# 4_viper_eagle_modern_periferals.net
KiCad netlist of a schematic drawn in Altium Designer
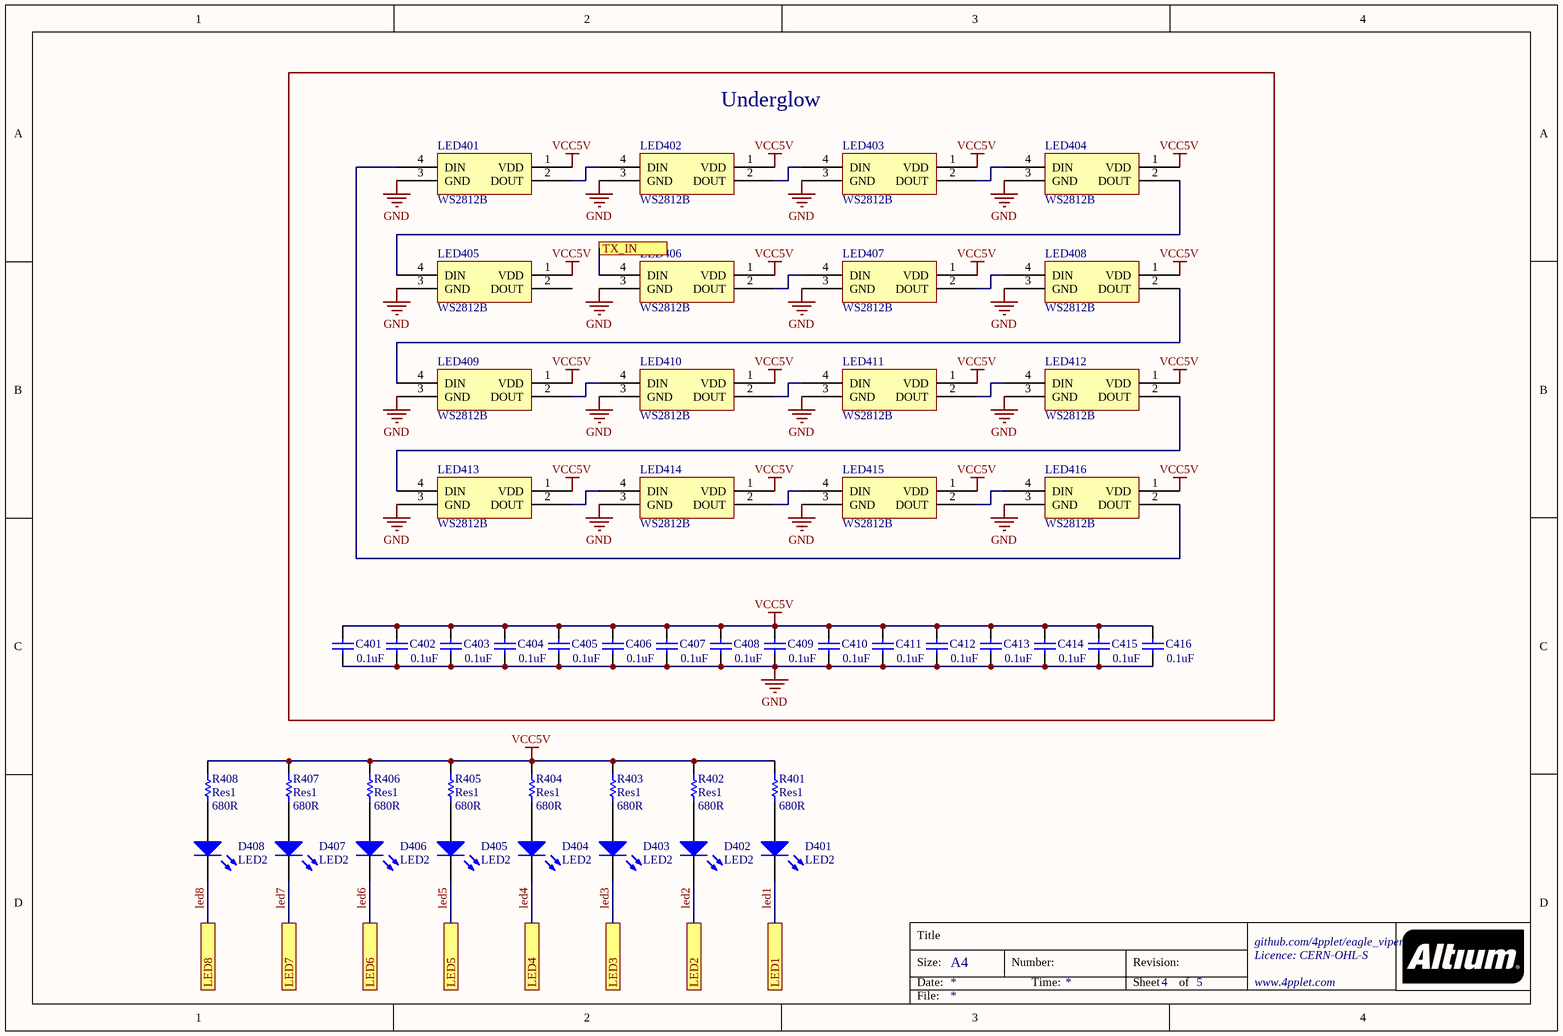
[diagram p0: 4_viper_eagle_modern_periferals.SchDoc]

(export (version "E")
  (design (tool "Eeschema 10.0.6"))
  (components
    (comp (ref "C401")
      (value "0.1uF")
      (footprint "C0603[1608]")
      (description "Capacitor")
      (fields (field (name "MFG") "KEMET") (field (name "LCSC PART #") "C14663"))
      (libsource (lib "Miscellaneous Devices") (part "Cap"))
    )
    (comp (ref "C402")
      (value "0.1uF")
      (footprint "C0603[1608]")
      (description "Capacitor")
      (fields (field (name "MFG") "KEMET") (field (name "LCSC PART #") "C14663"))
      (libsource (lib "Miscellaneous Devices") (part "Cap"))
    )
    (comp (ref "C403")
      (value "0.1uF")
      (footprint "C0603[1608]")
      (description "Capacitor")
      (fields (field (name "MFG") "KEMET") (field (name "LCSC PART #") "C14663"))
      (libsource (lib "Miscellaneous Devices") (part "Cap"))
    )
    (comp (ref "C404")
      (value "0.1uF")
      (footprint "C0603[1608]")
      (description "Capacitor")
      (fields (field (name "MFG") "KEMET") (field (name "LCSC PART #") "C14663"))
      (libsource (lib "Miscellaneous Devices") (part "Cap"))
    )
    (comp (ref "C405")
      (value "0.1uF")
      (footprint "C0603[1608]")
      (description "Capacitor")
      (fields (field (name "MFG") "KEMET") (field (name "LCSC PART #") "C14663"))
      (libsource (lib "Miscellaneous Devices") (part "Cap"))
    )
    (comp (ref "C406")
      (value "0.1uF")
      (footprint "C0603[1608]")
      (description "Capacitor")
      (fields (field (name "MFG") "KEMET") (field (name "LCSC PART #") "C14663"))
      (libsource (lib "Miscellaneous Devices") (part "Cap"))
    )
    (comp (ref "C407")
      (value "0.1uF")
      (footprint "C0603[1608]")
      (description "Capacitor")
      (fields (field (name "MFG") "KEMET") (field (name "LCSC PART #") "C14663"))
      (libsource (lib "Miscellaneous Devices") (part "Cap"))
    )
    (comp (ref "C408")
      (value "0.1uF")
      (footprint "C0603[1608]")
      (description "Capacitor")
      (fields (field (name "MFG") "KEMET") (field (name "LCSC PART #") "C14663"))
      (libsource (lib "Miscellaneous Devices") (part "Cap"))
    )
    (comp (ref "C409")
      (value "0.1uF")
      (footprint "C0603[1608]")
      (description "Capacitor")
      (fields (field (name "MFG") "KEMET") (field (name "LCSC PART #") "C14663"))
      (libsource (lib "Miscellaneous Devices") (part "Cap"))
    )
    (comp (ref "C410")
      (value "0.1uF")
      (footprint "C0603[1608]")
      (description "Capacitor")
      (fields (field (name "MFG") "KEMET") (field (name "LCSC PART #") "C14663"))
      (libsource (lib "Miscellaneous Devices") (part "Cap"))
    )
    (comp (ref "C411")
      (value "0.1uF")
      (footprint "C0603[1608]")
      (description "Capacitor")
      (fields (field (name "MFG") "KEMET") (field (name "LCSC PART #") "C14663"))
      (libsource (lib "Miscellaneous Devices") (part "Cap"))
    )
    (comp (ref "C412")
      (value "0.1uF")
      (footprint "C0603[1608]")
      (description "Capacitor")
      (fields (field (name "MFG") "KEMET") (field (name "LCSC PART #") "C14663"))
      (libsource (lib "Miscellaneous Devices") (part "Cap"))
    )
    (comp (ref "C413")
      (value "0.1uF")
      (footprint "C0603[1608]")
      (description "Capacitor")
      (fields (field (name "MFG") "KEMET") (field (name "LCSC PART #") "C14663"))
      (libsource (lib "Miscellaneous Devices") (part "Cap"))
    )
    (comp (ref "C414")
      (value "0.1uF")
      (footprint "C0603[1608]")
      (description "Capacitor")
      (fields (field (name "MFG") "KEMET") (field (name "LCSC PART #") "C14663"))
      (libsource (lib "Miscellaneous Devices") (part "Cap"))
    )
    (comp (ref "C415")
      (value "0.1uF")
      (footprint "C0603[1608]")
      (description "Capacitor")
      (fields (field (name "MFG") "KEMET") (field (name "LCSC PART #") "C14663"))
      (libsource (lib "Miscellaneous Devices") (part "Cap"))
    )
    (comp (ref "C416")
      (value "0.1uF")
      (footprint "C0603[1608]")
      (description "Capacitor")
      (fields (field (name "MFG") "KEMET") (field (name "LCSC PART #") "C14663"))
      (libsource (lib "Miscellaneous Devices") (part "Cap"))
    )
    (comp (ref "D401")
      (value "LED2")
      (footprint "LED - THT")
      (description "Typical RED, GREEN, YELLOW, AMBER GaAs LED")
      (libsource (lib "Miscellaneous Devices") (part "LED2"))
    )
    (comp (ref "D402")
      (value "LED2")
      (footprint "LED - THT")
      (description "Typical RED, GREEN, YELLOW, AMBER GaAs LED")
      (libsource (lib "Miscellaneous Devices") (part "LED2"))
    )
    (comp (ref "D403")
      (value "LED2")
      (footprint "LED - THT")
      (description "Typical RED, GREEN, YELLOW, AMBER GaAs LED")
      (libsource (lib "Miscellaneous Devices") (part "LED2"))
    )
    (comp (ref "D404")
      (value "LED2")
      (footprint "LED - THT")
      (description "Typical RED, GREEN, YELLOW, AMBER GaAs LED")
      (libsource (lib "Miscellaneous Devices") (part "LED2"))
    )
    (comp (ref "D405")
      (value "LED2")
      (footprint "LED - THT")
      (description "Typical RED, GREEN, YELLOW, AMBER GaAs LED")
      (libsource (lib "Miscellaneous Devices") (part "LED2"))
    )
    (comp (ref "D406")
      (value "LED2")
      (footprint "LED - THT")
      (description "Typical RED, GREEN, YELLOW, AMBER GaAs LED")
      (libsource (lib "Miscellaneous Devices") (part "LED2"))
    )
    (comp (ref "D407")
      (value "LED2")
      (footprint "LED - THT")
      (description "Typical RED, GREEN, YELLOW, AMBER GaAs LED")
      (libsource (lib "Miscellaneous Devices") (part "LED2"))
    )
    (comp (ref "D408")
      (value "LED2")
      (footprint "LED - THT")
      (description "Typical RED, GREEN, YELLOW, AMBER GaAs LED")
      (libsource (lib "Miscellaneous Devices") (part "LED2"))
    )
    (comp (ref "LED401")
      (value "WS2812B")
      (footprint "WS2812B")
      (fields (field (name "LCSC PART #") "C114586") (field (name "MRF.PART") "WS2812B-B"))
      (libsource (lib "Keebs") (part "WS2812B"))
    )
    (comp (ref "LED402")
      (value "WS2812B")
      (footprint "WS2812B")
      (fields (field (name "LCSC PART #") "C114586") (field (name "MRF.PART") "WS2812B-B"))
      (libsource (lib "Keebs") (part "WS2812B"))
    )
    (comp (ref "LED403")
      (value "WS2812B")
      (footprint "WS2812B")
      (fields (field (name "LCSC PART #") "C114586") (field (name "MRF.PART") "WS2812B-B"))
      (libsource (lib "Keebs") (part "WS2812B"))
    )
    (comp (ref "LED404")
      (value "WS2812B")
      (footprint "WS2812B")
      (fields (field (name "LCSC PART #") "C114586") (field (name "MRF.PART") "WS2812B-B"))
      (libsource (lib "Keebs") (part "WS2812B"))
    )
    (comp (ref "LED405")
      (value "WS2812B")
      (footprint "WS2812B")
      (fields (field (name "LCSC PART #") "C114586") (field (name "MRF.PART") "WS2812B-B"))
      (libsource (lib "Keebs") (part "WS2812B"))
    )
    (comp (ref "LED406")
      (value "WS2812B")
      (footprint "WS2812B")
      (fields (field (name "LCSC PART #") "C114586") (field (name "MRF.PART") "WS2812B-B"))
      (libsource (lib "Keebs") (part "WS2812B"))
    )
    (comp (ref "LED407")
      (value "WS2812B")
      (footprint "WS2812B")
      (fields (field (name "LCSC PART #") "C114586") (field (name "MRF.PART") "WS2812B-B"))
      (libsource (lib "Keebs") (part "WS2812B"))
    )
    (comp (ref "LED408")
      (value "WS2812B")
      (footprint "WS2812B")
      (fields (field (name "LCSC PART #") "C114586") (field (name "MRF.PART") "WS2812B-B"))
      (libsource (lib "Keebs") (part "WS2812B"))
    )
    (comp (ref "LED409")
      (value "WS2812B")
      (footprint "WS2812B")
      (fields (field (name "LCSC PART #") "C114586") (field (name "MRF.PART") "WS2812B-B"))
      (libsource (lib "Keebs") (part "WS2812B"))
    )
    (comp (ref "LED410")
      (value "WS2812B")
      (footprint "WS2812B")
      (fields (field (name "LCSC PART #") "C114586") (field (name "MRF.PART") "WS2812B-B"))
      (libsource (lib "Keebs") (part "WS2812B"))
    )
    (comp (ref "LED411")
      (value "WS2812B")
      (footprint "WS2812B")
      (fields (field (name "LCSC PART #") "C114586") (field (name "MRF.PART") "WS2812B-B"))
      (libsource (lib "Keebs") (part "WS2812B"))
    )
    (comp (ref "LED412")
      (value "WS2812B")
      (footprint "WS2812B")
      (fields (field (name "LCSC PART #") "C114586") (field (name "MRF.PART") "WS2812B-B"))
      (libsource (lib "Keebs") (part "WS2812B"))
    )
    (comp (ref "LED413")
      (value "WS2812B")
      (footprint "WS2812B")
      (fields (field (name "LCSC PART #") "C114586") (field (name "MRF.PART") "WS2812B-B"))
      (libsource (lib "Keebs") (part "WS2812B"))
    )
    (comp (ref "LED414")
      (value "WS2812B")
      (footprint "WS2812B")
      (fields (field (name "LCSC PART #") "C114586") (field (name "MRF.PART") "WS2812B-B"))
      (libsource (lib "Keebs") (part "WS2812B"))
    )
    (comp (ref "LED415")
      (value "WS2812B")
      (footprint "WS2812B")
      (fields (field (name "LCSC PART #") "C114586") (field (name "MRF.PART") "WS2812B-B"))
      (libsource (lib "Keebs") (part "WS2812B"))
    )
    (comp (ref "LED416")
      (value "WS2812B")
      (footprint "WS2812B")
      (fields (field (name "LCSC PART #") "C114586") (field (name "MRF.PART") "WS2812B-B"))
      (libsource (lib "Keebs") (part "WS2812B"))
    )
    (comp (ref "R401")
      (value "Res1")
      (footprint "R0603[1608]")
      (description "Resistor")
      (fields
        (field (name "ALTIUM_VALUE") "680R")
        (field (name "LCSC PART #") "C23228")
        (field (name "MRF.PART") "0603WAF6800T5E")
      )
      (libsource (lib "Miscellaneous Devices") (part "Res1"))
    )
    (comp (ref "R402")
      (value "Res1")
      (footprint "R0603[1608]")
      (description "Resistor")
      (fields
        (field (name "ALTIUM_VALUE") "680R")
        (field (name "LCSC PART #") "C23228")
        (field (name "MRF.PART") "0603WAF6800T5E")
      )
      (libsource (lib "Miscellaneous Devices") (part "Res1"))
    )
    (comp (ref "R403")
      (value "Res1")
      (footprint "R0603[1608]")
      (description "Resistor")
      (fields
        (field (name "ALTIUM_VALUE") "680R")
        (field (name "LCSC PART #") "C23228")
        (field (name "MRF.PART") "0603WAF6800T5E")
      )
      (libsource (lib "Miscellaneous Devices") (part "Res1"))
    )
    (comp (ref "R404")
      (value "Res1")
      (footprint "R0603[1608]")
      (description "Resistor")
      (fields
        (field (name "ALTIUM_VALUE") "680R")
        (field (name "LCSC PART #") "C23228")
        (field (name "MRF.PART") "0603WAF6800T5E")
      )
      (libsource (lib "Miscellaneous Devices") (part "Res1"))
    )
    (comp (ref "R405")
      (value "Res1")
      (footprint "R0603[1608]")
      (description "Resistor")
      (fields
        (field (name "ALTIUM_VALUE") "680R")
        (field (name "LCSC PART #") "C23228")
        (field (name "MRF.PART") "0603WAF6800T5E")
      )
      (libsource (lib "Miscellaneous Devices") (part "Res1"))
    )
    (comp (ref "R406")
      (value "Res1")
      (footprint "R0603[1608]")
      (description "Resistor")
      (fields
        (field (name "ALTIUM_VALUE") "680R")
        (field (name "LCSC PART #") "C23228")
        (field (name "MRF.PART") "0603WAF6800T5E")
      )
      (libsource (lib "Miscellaneous Devices") (part "Res1"))
    )
    (comp (ref "R407")
      (value "Res1")
      (footprint "R0603[1608]")
      (description "Resistor")
      (fields
        (field (name "ALTIUM_VALUE") "680R")
        (field (name "LCSC PART #") "C23228")
        (field (name "MRF.PART") "0603WAF6800T5E")
      )
      (libsource (lib "Miscellaneous Devices") (part "Res1"))
    )
    (comp (ref "R408")
      (value "Res1")
      (footprint "R0603[1608]")
      (description "Resistor")
      (fields
        (field (name "ALTIUM_VALUE") "680R")
        (field (name "LCSC PART #") "C23228")
        (field (name "MRF.PART") "0603WAF6800T5E")
      )
      (libsource (lib "Miscellaneous Devices") (part "Res1"))
    )
  )
  (nets
    (net (code "1") (name "/TX_IN") (class "Default")
      (node (ref "LED406") (pin "4") (pinfunction "DIN_4") (pintype "passive"))
    )
    (net (code "2") (name "/led1") (class "Default")
      (node (ref "D401") (pin "2") (pinfunction "K_2") (pintype "passive"))
    )
    (net (code "3") (name "/led2") (class "Default")
      (node (ref "D402") (pin "2") (pinfunction "K_2") (pintype "passive"))
    )
    (net (code "4") (name "/led3") (class "Default")
      (node (ref "D403") (pin "2") (pinfunction "K_2") (pintype "passive"))
    )
    (net (code "5") (name "/led4") (class "Default")
      (node (ref "D404") (pin "2") (pinfunction "K_2") (pintype "passive"))
    )
    (net (code "6") (name "/led5") (class "Default")
      (node (ref "D405") (pin "2") (pinfunction "K_2") (pintype "passive"))
    )
    (net (code "7") (name "/led6") (class "Default")
      (node (ref "D406") (pin "2") (pinfunction "K_2") (pintype "passive"))
    )
    (net (code "8") (name "/led7") (class "Default")
      (node (ref "D407") (pin "2") (pinfunction "K_2") (pintype "passive"))
    )
    (net (code "9") (name "/led8") (class "Default")
      (node (ref "D408") (pin "2") (pinfunction "K_2") (pintype "passive"))
    )
    (net (code "10") (name "GND") (class "Default")
      (node (ref "C401") (pin "1") (pinfunction "1_1") (pintype "passive"))
      (node (ref "C402") (pin "1") (pinfunction "1_1") (pintype "passive"))
      (node (ref "C403") (pin "1") (pinfunction "1_1") (pintype "passive"))
      (node (ref "C404") (pin "1") (pinfunction "1_1") (pintype "passive"))
      (node (ref "C405") (pin "1") (pinfunction "1_1") (pintype "passive"))
      (node (ref "C406") (pin "1") (pinfunction "1_1") (pintype "passive"))
      (node (ref "C407") (pin "1") (pinfunction "1_1") (pintype "passive"))
      (node (ref "C408") (pin "1") (pinfunction "1_1") (pintype "passive"))
      (node (ref "C409") (pin "1") (pinfunction "1_1") (pintype "passive"))
      (node (ref "C410") (pin "1") (pinfunction "1_1") (pintype "passive"))
      (node (ref "C411") (pin "1") (pinfunction "1_1") (pintype "passive"))
      (node (ref "C412") (pin "1") (pinfunction "1_1") (pintype "passive"))
      (node (ref "C413") (pin "1") (pinfunction "1_1") (pintype "passive"))
      (node (ref "C414") (pin "1") (pinfunction "1_1") (pintype "passive"))
      (node (ref "C415") (pin "1") (pinfunction "1_1") (pintype "passive"))
      (node (ref "C416") (pin "1") (pinfunction "1_1") (pintype "passive"))
      (node (ref "LED401") (pin "3") (pinfunction "GND_3") (pintype "passive"))
      (node (ref "LED402") (pin "3") (pinfunction "GND_3") (pintype "passive"))
      (node (ref "LED403") (pin "3") (pinfunction "GND_3") (pintype "passive"))
      (node (ref "LED404") (pin "3") (pinfunction "GND_3") (pintype "passive"))
      (node (ref "LED405") (pin "3") (pinfunction "GND_3") (pintype "passive"))
      (node (ref "LED406") (pin "3") (pinfunction "GND_3") (pintype "passive"))
      (node (ref "LED407") (pin "3") (pinfunction "GND_3") (pintype "passive"))
      (node (ref "LED408") (pin "3") (pinfunction "GND_3") (pintype "passive"))
      (node (ref "LED409") (pin "3") (pinfunction "GND_3") (pintype "passive"))
      (node (ref "LED410") (pin "3") (pinfunction "GND_3") (pintype "passive"))
      (node (ref "LED411") (pin "3") (pinfunction "GND_3") (pintype "passive"))
      (node (ref "LED412") (pin "3") (pinfunction "GND_3") (pintype "passive"))
      (node (ref "LED413") (pin "3") (pinfunction "GND_3") (pintype "passive"))
      (node (ref "LED414") (pin "3") (pinfunction "GND_3") (pintype "passive"))
      (node (ref "LED415") (pin "3") (pinfunction "GND_3") (pintype "passive"))
      (node (ref "LED416") (pin "3") (pinfunction "GND_3") (pintype "passive"))
    )
    (net (code "11") (name "Net-(D401-A)") (class "Default")
      (node (ref "D401") (pin "1") (pinfunction "A_1") (pintype "passive"))
      (node (ref "R401") (pin "2") (pinfunction "2_2") (pintype "passive"))
    )
    (net (code "12") (name "Net-(D402-A)") (class "Default")
      (node (ref "D402") (pin "1") (pinfunction "A_1") (pintype "passive"))
      (node (ref "R402") (pin "2") (pinfunction "2_2") (pintype "passive"))
    )
    (net (code "13") (name "Net-(D403-A)") (class "Default")
      (node (ref "D403") (pin "1") (pinfunction "A_1") (pintype "passive"))
      (node (ref "R403") (pin "2") (pinfunction "2_2") (pintype "passive"))
    )
    (net (code "14") (name "Net-(D404-A)") (class "Default")
      (node (ref "D404") (pin "1") (pinfunction "A_1") (pintype "passive"))
      (node (ref "R404") (pin "2") (pinfunction "2_2") (pintype "passive"))
    )
    (net (code "15") (name "Net-(D405-A)") (class "Default")
      (node (ref "D405") (pin "1") (pinfunction "A_1") (pintype "passive"))
      (node (ref "R405") (pin "2") (pinfunction "2_2") (pintype "passive"))
    )
    (net (code "16") (name "Net-(D406-A)") (class "Default")
      (node (ref "D406") (pin "1") (pinfunction "A_1") (pintype "passive"))
      (node (ref "R406") (pin "2") (pinfunction "2_2") (pintype "passive"))
    )
    (net (code "17") (name "Net-(D407-A)") (class "Default")
      (node (ref "D407") (pin "1") (pinfunction "A_1") (pintype "passive"))
      (node (ref "R407") (pin "2") (pinfunction "2_2") (pintype "passive"))
    )
    (net (code "18") (name "Net-(D408-A)") (class "Default")
      (node (ref "D408") (pin "1") (pinfunction "A_1") (pintype "passive"))
      (node (ref "R408") (pin "2") (pinfunction "2_2") (pintype "passive"))
    )
    (net (code "19") (name "Net-(LED401-DIN)") (class "Default")
      (node (ref "LED401") (pin "4") (pinfunction "DIN_4") (pintype "passive"))
      (node (ref "LED416") (pin "2") (pinfunction "DOUT_2") (pintype "passive"))
    )
    (net (code "20") (name "Net-(LED401-DOUT)") (class "Default")
      (node (ref "LED401") (pin "2") (pinfunction "DOUT_2") (pintype "passive"))
      (node (ref "LED402") (pin "4") (pinfunction "DIN_4") (pintype "passive"))
    )
    (net (code "21") (name "Net-(LED402-DOUT)") (class "Default")
      (node (ref "LED402") (pin "2") (pinfunction "DOUT_2") (pintype "passive"))
      (node (ref "LED403") (pin "4") (pinfunction "DIN_4") (pintype "passive"))
    )
    (net (code "22") (name "Net-(LED403-DOUT)") (class "Default")
      (node (ref "LED403") (pin "2") (pinfunction "DOUT_2") (pintype "passive"))
      (node (ref "LED404") (pin "4") (pinfunction "DIN_4") (pintype "passive"))
    )
    (net (code "23") (name "Net-(LED404-DOUT)") (class "Default")
      (node (ref "LED404") (pin "2") (pinfunction "DOUT_2") (pintype "passive"))
      (node (ref "LED405") (pin "4") (pinfunction "DIN_4") (pintype "passive"))
    )
    (net (code "24") (name "Net-(LED406-DOUT)") (class "Default")
      (node (ref "LED406") (pin "2") (pinfunction "DOUT_2") (pintype "passive"))
      (node (ref "LED407") (pin "4") (pinfunction "DIN_4") (pintype "passive"))
    )
    (net (code "25") (name "Net-(LED407-DOUT)") (class "Default")
      (node (ref "LED407") (pin "2") (pinfunction "DOUT_2") (pintype "passive"))
      (node (ref "LED408") (pin "4") (pinfunction "DIN_4") (pintype "passive"))
    )
    (net (code "26") (name "Net-(LED408-DOUT)") (class "Default")
      (node (ref "LED408") (pin "2") (pinfunction "DOUT_2") (pintype "passive"))
      (node (ref "LED409") (pin "4") (pinfunction "DIN_4") (pintype "passive"))
    )
    (net (code "27") (name "Net-(LED409-DOUT)") (class "Default")
      (node (ref "LED409") (pin "2") (pinfunction "DOUT_2") (pintype "passive"))
      (node (ref "LED410") (pin "4") (pinfunction "DIN_4") (pintype "passive"))
    )
    (net (code "28") (name "Net-(LED410-DOUT)") (class "Default")
      (node (ref "LED410") (pin "2") (pinfunction "DOUT_2") (pintype "passive"))
      (node (ref "LED411") (pin "4") (pinfunction "DIN_4") (pintype "passive"))
    )
    (net (code "29") (name "Net-(LED411-DOUT)") (class "Default")
      (node (ref "LED411") (pin "2") (pinfunction "DOUT_2") (pintype "passive"))
      (node (ref "LED412") (pin "4") (pinfunction "DIN_4") (pintype "passive"))
    )
    (net (code "30") (name "Net-(LED412-DOUT)") (class "Default")
      (node (ref "LED412") (pin "2") (pinfunction "DOUT_2") (pintype "passive"))
      (node (ref "LED413") (pin "4") (pinfunction "DIN_4") (pintype "passive"))
    )
    (net (code "31") (name "Net-(LED413-DOUT)") (class "Default")
      (node (ref "LED413") (pin "2") (pinfunction "DOUT_2") (pintype "passive"))
      (node (ref "LED414") (pin "4") (pinfunction "DIN_4") (pintype "passive"))
    )
    (net (code "32") (name "Net-(LED414-DOUT)") (class "Default")
      (node (ref "LED414") (pin "2") (pinfunction "DOUT_2") (pintype "passive"))
      (node (ref "LED415") (pin "4") (pinfunction "DIN_4") (pintype "passive"))
    )
    (net (code "33") (name "Net-(LED415-DOUT)") (class "Default")
      (node (ref "LED415") (pin "2") (pinfunction "DOUT_2") (pintype "passive"))
      (node (ref "LED416") (pin "4") (pinfunction "DIN_4") (pintype "passive"))
    )
    (net (code "34") (name "VCC5V") (class "Default")
      (node (ref "C401") (pin "2") (pinfunction "2_2") (pintype "passive"))
      (node (ref "C402") (pin "2") (pinfunction "2_2") (pintype "passive"))
      (node (ref "C403") (pin "2") (pinfunction "2_2") (pintype "passive"))
      (node (ref "C404") (pin "2") (pinfunction "2_2") (pintype "passive"))
      (node (ref "C405") (pin "2") (pinfunction "2_2") (pintype "passive"))
      (node (ref "C406") (pin "2") (pinfunction "2_2") (pintype "passive"))
      (node (ref "C407") (pin "2") (pinfunction "2_2") (pintype "passive"))
      (node (ref "C408") (pin "2") (pinfunction "2_2") (pintype "passive"))
      (node (ref "C409") (pin "2") (pinfunction "2_2") (pintype "passive"))
      (node (ref "C410") (pin "2") (pinfunction "2_2") (pintype "passive"))
      (node (ref "C411") (pin "2") (pinfunction "2_2") (pintype "passive"))
      (node (ref "C412") (pin "2") (pinfunction "2_2") (pintype "passive"))
      (node (ref "C413") (pin "2") (pinfunction "2_2") (pintype "passive"))
      (node (ref "C414") (pin "2") (pinfunction "2_2") (pintype "passive"))
      (node (ref "C415") (pin "2") (pinfunction "2_2") (pintype "passive"))
      (node (ref "C416") (pin "2") (pinfunction "2_2") (pintype "passive"))
      (node (ref "LED401") (pin "1") (pinfunction "VDD_1") (pintype "passive"))
      (node (ref "LED402") (pin "1") (pinfunction "VDD_1") (pintype "passive"))
      (node (ref "LED403") (pin "1") (pinfunction "VDD_1") (pintype "passive"))
      (node (ref "LED404") (pin "1") (pinfunction "VDD_1") (pintype "passive"))
      (node (ref "LED405") (pin "1") (pinfunction "VDD_1") (pintype "passive"))
      (node (ref "LED406") (pin "1") (pinfunction "VDD_1") (pintype "passive"))
      (node (ref "LED407") (pin "1") (pinfunction "VDD_1") (pintype "passive"))
      (node (ref "LED408") (pin "1") (pinfunction "VDD_1") (pintype "passive"))
      (node (ref "LED409") (pin "1") (pinfunction "VDD_1") (pintype "passive"))
      (node (ref "LED410") (pin "1") (pinfunction "VDD_1") (pintype "passive"))
      (node (ref "LED411") (pin "1") (pinfunction "VDD_1") (pintype "passive"))
      (node (ref "LED412") (pin "1") (pinfunction "VDD_1") (pintype "passive"))
      (node (ref "LED413") (pin "1") (pinfunction "VDD_1") (pintype "passive"))
      (node (ref "LED414") (pin "1") (pinfunction "VDD_1") (pintype "passive"))
      (node (ref "LED415") (pin "1") (pinfunction "VDD_1") (pintype "passive"))
      (node (ref "LED416") (pin "1") (pinfunction "VDD_1") (pintype "passive"))
      (node (ref "R401") (pin "1") (pinfunction "1_1") (pintype "passive"))
      (node (ref "R402") (pin "1") (pinfunction "1_1") (pintype "passive"))
      (node (ref "R403") (pin "1") (pinfunction "1_1") (pintype "passive"))
      (node (ref "R404") (pin "1") (pinfunction "1_1") (pintype "passive"))
      (node (ref "R405") (pin "1") (pinfunction "1_1") (pintype "passive"))
      (node (ref "R406") (pin "1") (pinfunction "1_1") (pintype "passive"))
      (node (ref "R407") (pin "1") (pinfunction "1_1") (pintype "passive"))
      (node (ref "R408") (pin "1") (pinfunction "1_1") (pintype "passive"))
    )
    (net (code "35") (name "unconnected-(LED405-DOUT-Pad2)") (class "Default")
      (node (ref "LED405") (pin "2") (pinfunction "DOUT_2") (pintype "passive"))
    )
  )
)
